# termoresistenza_v1_rev1.net
KiCad netlist of a schematic drawn in EAGLE
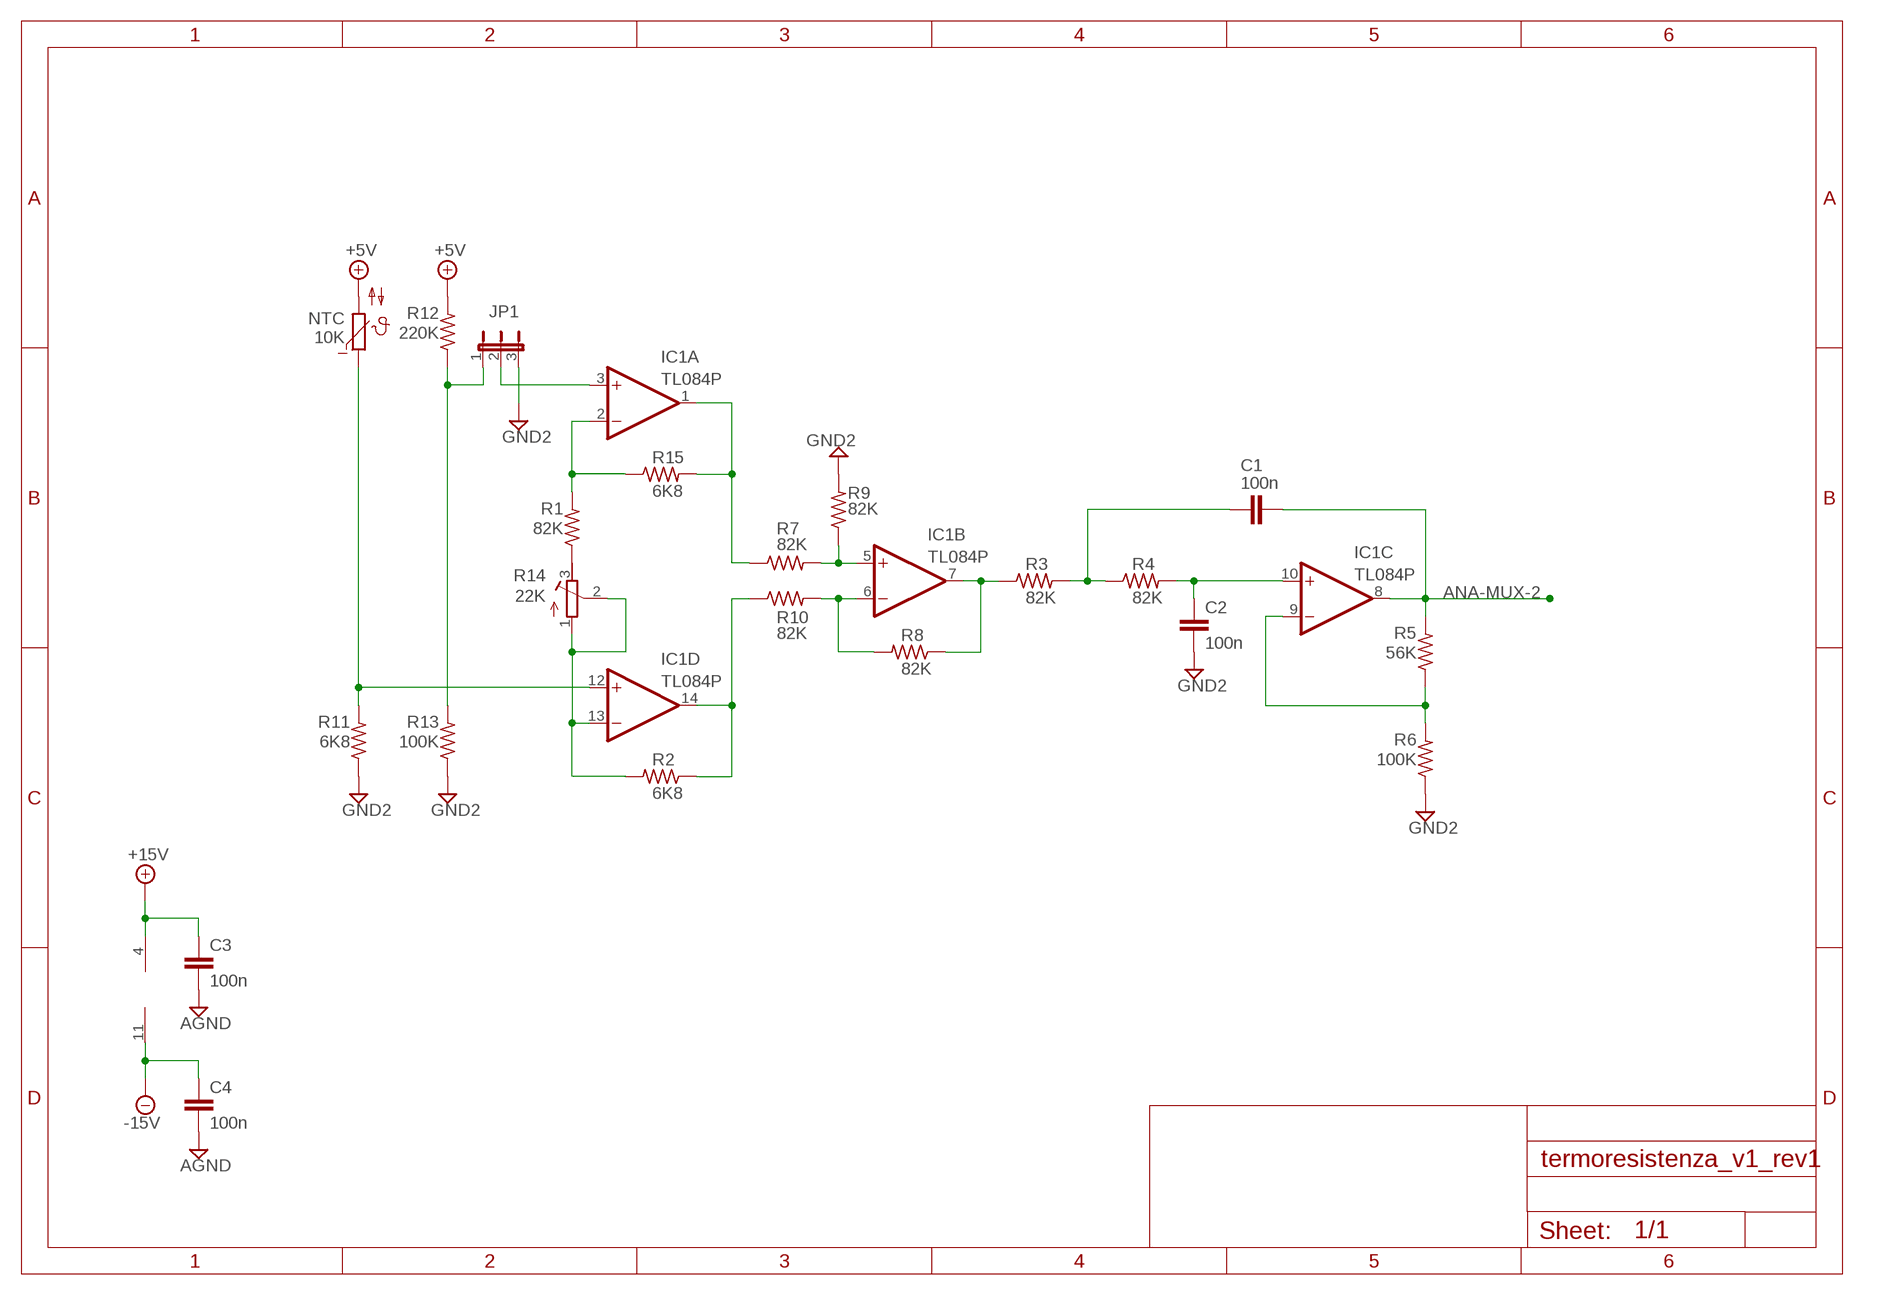
[diagram p0: schematic, sheet 1]

(export (version "E")
  (design (tool "Eeschema 10.0.6"))
  (components
    (comp (ref "C1")
      (value "100n")
      (footprint "eagle-import:C025-025X050")
      (libsource (lib "eagle-import") (part "C-EU025-025X050"))
    )
    (comp (ref "C2")
      (value "100n")
      (footprint "eagle-import:C025-025X050")
      (libsource (lib "eagle-import") (part "C-EU025-025X050"))
    )
    (comp (ref "C3")
      (value "100n")
      (footprint "eagle-import:C025-025X050")
      (libsource (lib "eagle-import") (part "C-EU025-025X050"))
    )
    (comp (ref "C4")
      (value "100n")
      (footprint "eagle-import:C025-025X050")
      (libsource (lib "eagle-import") (part "C-EU025-025X050"))
    )
    (comp (ref "IC1")
      (value "TL084P")
      (footprint "eagle-import:DIL14")
      (libsource (lib "eagle-import") (part "TL084P"))
    )
    (comp (ref "JP1")
      (value "JP2E")
      (footprint "eagle-import:JP2")
      (libsource (lib "eagle-import") (part "JP2E"))
    )
    (comp (ref "NTC")
      (value "10K")
      (footprint "eagle-import:P640")
      (libsource (lib "eagle-import") (part "NTC640"))
    )
    (comp (ref "R1")
      (value "82K")
      (footprint "eagle-import:0204_7")
      (libsource (lib "eagle-import") (part "R-US_0204/7"))
    )
    (comp (ref "R2")
      (value "6K8")
      (footprint "eagle-import:0204_7")
      (libsource (lib "eagle-import") (part "R-US_0204/7"))
    )
    (comp (ref "R3")
      (value "82K")
      (footprint "eagle-import:0204_7")
      (libsource (lib "eagle-import") (part "R-US_0204/7"))
    )
    (comp (ref "R4")
      (value "82K")
      (footprint "eagle-import:0204_7")
      (libsource (lib "eagle-import") (part "R-US_0204/7"))
    )
    (comp (ref "R5")
      (value "56K")
      (footprint "eagle-import:0204_7")
      (libsource (lib "eagle-import") (part "R-US_0204/7"))
    )
    (comp (ref "R6")
      (value "100K")
      (footprint "eagle-import:0204_7")
      (libsource (lib "eagle-import") (part "R-US_0204/7"))
    )
    (comp (ref "R7")
      (value "82K")
      (footprint "eagle-import:0204_7")
      (libsource (lib "eagle-import") (part "R-US_0204/7"))
    )
    (comp (ref "R8")
      (value "82K")
      (footprint "eagle-import:0204_7")
      (libsource (lib "eagle-import") (part "R-US_0204/7"))
    )
    (comp (ref "R9")
      (value "82K")
      (footprint "eagle-import:0204_7")
      (libsource (lib "eagle-import") (part "R-US_0204/7"))
    )
    (comp (ref "R10")
      (value "82K")
      (footprint "eagle-import:0204_7")
      (libsource (lib "eagle-import") (part "R-US_0204/7"))
    )
    (comp (ref "R11")
      (value "6K8")
      (footprint "eagle-import:0204_7")
      (libsource (lib "eagle-import") (part "R-US_0204/7"))
    )
    (comp (ref "R12")
      (value "220K")
      (footprint "eagle-import:0204_7")
      (libsource (lib "eagle-import") (part "R-US_0204/7"))
    )
    (comp (ref "R13")
      (value "100K")
      (footprint "eagle-import:0204_7")
      (libsource (lib "eagle-import") (part "R-US_0204/7"))
    )
    (comp (ref "R14")
      (value "22K")
      (footprint "eagle-import:RTRIM64W")
      (libsource (lib "eagle-import") (part "R-TRIMM64W"))
    )
    (comp (ref "R15")
      (value "6K8")
      (footprint "eagle-import:0204_7")
      (libsource (lib "eagle-import") (part "R-US_0204/7"))
    )
  )
  (nets
    (net (code "1") (name "+5V") (class "Default")
      (node (ref "NTC") (pin "2") (pinfunction "2_2") (pintype "passive"))
      (node (ref "R12") (pin "2") (pinfunction "2_2") (pintype "passive"))
    )
    (net (code "2") (name "+15V") (class "Default")
      (node (ref "C3") (pin "1") (pinfunction "1_1") (pintype "passive"))
      (node (ref "IC1") (pin "4") (pinfunction "V+_4") (pintype "power_in"))
    )
    (net (code "3") (name "-15V") (class "Default")
      (node (ref "C4") (pin "1") (pinfunction "1_1") (pintype "passive"))
      (node (ref "IC1") (pin "11") (pinfunction "V-_11") (pintype "power_in"))
    )
    (net (code "4") (name "/ANA-MUX-2") (class "Default")
      (node (ref "C1") (pin "2") (pinfunction "2_2") (pintype "passive"))
      (node (ref "IC1") (pin "8") (pinfunction "OUT_8") (pintype "output"))
      (node (ref "R5") (pin "2") (pinfunction "2_2") (pintype "passive"))
    )
    (net (code "5") (name "AGND") (class "Default")
      (node (ref "C3") (pin "2") (pinfunction "2_2") (pintype "passive"))
      (node (ref "C4") (pin "2") (pinfunction "2_2") (pintype "passive"))
    )
    (net (code "6") (name "GND2") (class "Default")
      (node (ref "C2") (pin "2") (pinfunction "2_2") (pintype "passive"))
      (node (ref "JP1") (pin "3") (pinfunction "3_3") (pintype "passive"))
      (node (ref "R11") (pin "1") (pinfunction "1_1") (pintype "passive"))
      (node (ref "R13") (pin "1") (pinfunction "1_1") (pintype "passive"))
      (node (ref "R6") (pin "1") (pinfunction "1_1") (pintype "passive"))
      (node (ref "R9") (pin "2") (pinfunction "2_2") (pintype "passive"))
    )
    (net (code "7") (name "Net-(C1-Pad1)") (class "Default")
      (node (ref "C1") (pin "1") (pinfunction "1_1") (pintype "passive"))
      (node (ref "R3") (pin "2") (pinfunction "2_2") (pintype "passive"))
      (node (ref "R4") (pin "1") (pinfunction "1_1") (pintype "passive"))
    )
    (net (code "8") (name "Net-(IC1A-+IN)") (class "Default")
      (node (ref "IC1") (pin "3") (pinfunction "+IN_3") (pintype "input"))
      (node (ref "JP1") (pin "2") (pinfunction "2_2") (pintype "passive"))
    )
    (net (code "9") (name "Net-(IC1A--IN)") (class "Default")
      (node (ref "IC1") (pin "2") (pinfunction "-IN_2") (pintype "input"))
      (node (ref "R1") (pin "2") (pinfunction "2_2") (pintype "passive"))
      (node (ref "R15") (pin "1") (pinfunction "1_1") (pintype "passive"))
    )
    (net (code "10") (name "Net-(IC1A-OUT)") (class "Default")
      (node (ref "IC1") (pin "1") (pinfunction "OUT_1") (pintype "output"))
      (node (ref "R10") (pin "1") (pinfunction "1_1") (pintype "passive"))
      (node (ref "R15") (pin "2") (pinfunction "2_2") (pintype "passive"))
    )
    (net (code "11") (name "Net-(IC1B-+IN)") (class "Default")
      (node (ref "IC1") (pin "5") (pinfunction "+IN_5") (pintype "input"))
      (node (ref "R10") (pin "2") (pinfunction "2_2") (pintype "passive"))
      (node (ref "R9") (pin "1") (pinfunction "1_1") (pintype "passive"))
    )
    (net (code "12") (name "Net-(IC1B--IN)") (class "Default")
      (node (ref "IC1") (pin "6") (pinfunction "-IN_6") (pintype "input"))
      (node (ref "R7") (pin "2") (pinfunction "2_2") (pintype "passive"))
      (node (ref "R8") (pin "2") (pinfunction "2_2") (pintype "passive"))
    )
    (net (code "13") (name "Net-(IC1B-OUT)") (class "Default")
      (node (ref "IC1") (pin "7") (pinfunction "OUT_7") (pintype "output"))
      (node (ref "R3") (pin "1") (pinfunction "1_1") (pintype "passive"))
      (node (ref "R8") (pin "1") (pinfunction "1_1") (pintype "passive"))
    )
    (net (code "14") (name "Net-(IC1C-+IN)") (class "Default")
      (node (ref "C2") (pin "1") (pinfunction "1_1") (pintype "passive"))
      (node (ref "IC1") (pin "10") (pinfunction "+IN_10") (pintype "input"))
      (node (ref "R4") (pin "2") (pinfunction "2_2") (pintype "passive"))
    )
    (net (code "15") (name "Net-(IC1C--IN)") (class "Default")
      (node (ref "IC1") (pin "9") (pinfunction "-IN_9") (pintype "input"))
      (node (ref "R5") (pin "1") (pinfunction "1_1") (pintype "passive"))
      (node (ref "R6") (pin "2") (pinfunction "2_2") (pintype "passive"))
    )
    (net (code "16") (name "Net-(IC1D-+IN)") (class "Default")
      (node (ref "IC1") (pin "12") (pinfunction "+IN_12") (pintype "input"))
      (node (ref "NTC") (pin "1") (pinfunction "1_1") (pintype "passive"))
      (node (ref "R11") (pin "2") (pinfunction "2_2") (pintype "passive"))
    )
    (net (code "17") (name "Net-(IC1D--IN)") (class "Default")
      (node (ref "IC1") (pin "13") (pinfunction "-IN_13") (pintype "input"))
      (node (ref "R14") (pin "1") (pinfunction "E_1") (pintype "passive"))
      (node (ref "R14") (pin "2") (pinfunction "S_2") (pintype "passive"))
      (node (ref "R2") (pin "2") (pinfunction "2_2") (pintype "passive"))
    )
    (net (code "18") (name "Net-(IC1D-OUT)") (class "Default")
      (node (ref "IC1") (pin "14") (pinfunction "OUT_14") (pintype "output"))
      (node (ref "R2") (pin "1") (pinfunction "1_1") (pintype "passive"))
      (node (ref "R7") (pin "1") (pinfunction "1_1") (pintype "passive"))
    )
    (net (code "19") (name "Net-(JP1-Pad1)") (class "Default")
      (node (ref "JP1") (pin "1") (pinfunction "1_1") (pintype "passive"))
      (node (ref "R12") (pin "1") (pinfunction "1_1") (pintype "passive"))
      (node (ref "R13") (pin "2") (pinfunction "2_2") (pintype "passive"))
    )
    (net (code "20") (name "Net-(R14-A)") (class "Default")
      (node (ref "R1") (pin "1") (pinfunction "1_1") (pintype "passive"))
      (node (ref "R14") (pin "3") (pinfunction "A_3") (pintype "passive"))
    )
  )
)
